# iPlug.net
KiCad netlist of a schematic drawn in EAGLE
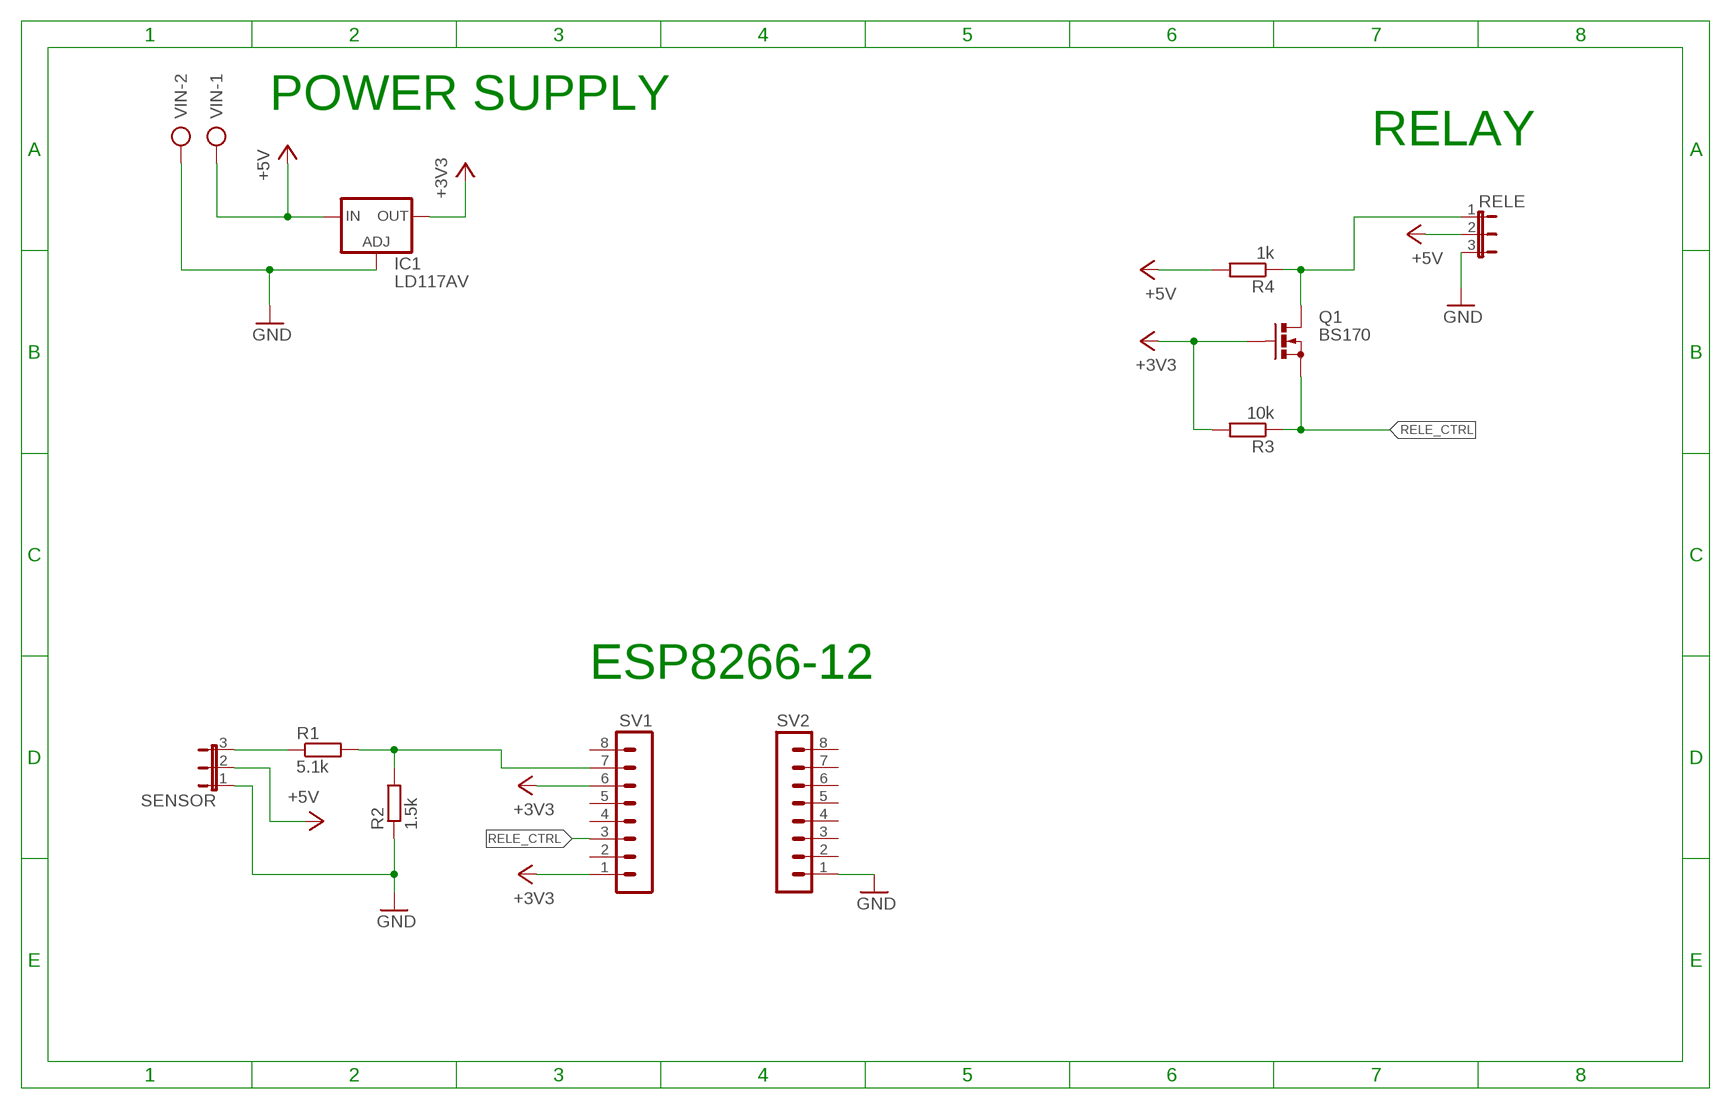
[diagram p0: schematic, sheet 1]

(export (version "E")
  (design (tool "Eeschema 10.0.6"))
  (components
    (comp (ref "IC1")
      (value "LD117AV")
      (footprint "eagle-import:TO220L1")
      (libsource (lib "eagle-import") (part "LD117A?V"))
    )
    (comp (ref "Q1")
      (value "BS170")
      (footprint "eagle-import:SOT54E")
      (libsource (lib "eagle-import") (part "BS170"))
    )
    (comp (ref "R1")
      (value "5.1k")
      (footprint "eagle-import:0207_10")
      (libsource (lib "eagle-import") (part "R-EU_0207/10"))
    )
    (comp (ref "R2")
      (value "1.5k")
      (footprint "eagle-import:0207_10")
      (libsource (lib "eagle-import") (part "R-EU_0207/10"))
    )
    (comp (ref "R3")
      (value "10k")
      (footprint "eagle-import:0207_10")
      (libsource (lib "eagle-import") (part "R-EU_0207/10"))
    )
    (comp (ref "R4")
      (value "1k")
      (footprint "eagle-import:0207_10")
      (libsource (lib "eagle-import") (part "R-EU_0207/10"))
    )
    (comp (ref "RELE")
      (value "JP2E")
      (footprint "eagle-import:JP2")
      (libsource (lib "eagle-import") (part "JP2E"))
    )
    (comp (ref "SENSOR")
      (value "JP2E")
      (footprint "eagle-import:JP2")
      (libsource (lib "eagle-import") (part "JP2E"))
    )
    (comp (ref "SV1")
      (value "MA08-1")
      (footprint "eagle-import:MA08-1")
      (libsource (lib "eagle-import") (part "MA08-1"))
    )
    (comp (ref "SV2")
      (value "MA08-1")
      (footprint "eagle-import:MA08-1")
      (libsource (lib "eagle-import") (part "MA08-1"))
    )
    (comp (ref "VIN")
      (value "AK500/2")
      (footprint "eagle-import:AK500_2")
      (libsource (lib "eagle-import") (part "AK500/2"))
    )
  )
  (nets
    (net (code "1") (name "+3V3") (class "Default")
      (node (ref "IC1") (pin "2") (pinfunction "OUT_2") (pintype "passive"))
      (node (ref "Q1") (pin "G") (pinfunction "G_G") (pintype "passive"))
      (node (ref "R3") (pin "2") (pinfunction "2_2") (pintype "passive"))
      (node (ref "SV1") (pin "1") (pinfunction "1_1") (pintype "passive"))
      (node (ref "SV1") (pin "6") (pinfunction "6_6") (pintype "passive"))
    )
    (net (code "2") (name "+5V") (class "Default")
      (node (ref "IC1") (pin "3") (pinfunction "IN_3") (pintype "input"))
      (node (ref "R4") (pin "2") (pinfunction "2_2") (pintype "passive"))
      (node (ref "RELE") (pin "2") (pinfunction "2_2") (pintype "passive"))
      (node (ref "SENSOR") (pin "2") (pinfunction "2_2") (pintype "passive"))
      (node (ref "VIN") (pin "1") (pinfunction "KL_1") (pintype "passive"))
    )
    (net (code "3") (name "GND") (class "Default")
      (node (ref "IC1") (pin "1") (pinfunction "ADJ_1") (pintype "input"))
      (node (ref "R2") (pin "1") (pinfunction "1_1") (pintype "passive"))
      (node (ref "RELE") (pin "3") (pinfunction "3_3") (pintype "passive"))
      (node (ref "SENSOR") (pin "1") (pinfunction "1_1") (pintype "passive"))
      (node (ref "SV2") (pin "1") (pinfunction "1_1") (pintype "passive"))
      (node (ref "VIN") (pin "2") (pinfunction "KL_2") (pintype "passive"))
    )
    (net (code "4") (name "Net-(Q1-PadD)") (class "Default")
      (node (ref "Q1") (pin "D") (pinfunction "D_D") (pintype "passive"))
      (node (ref "R4") (pin "1") (pinfunction "1_1") (pintype "passive"))
      (node (ref "RELE") (pin "1") (pinfunction "1_1") (pintype "passive"))
    )
    (net (code "5") (name "Net-(R1-Pad1)") (class "Default")
      (node (ref "R1") (pin "1") (pinfunction "1_1") (pintype "passive"))
      (node (ref "SENSOR") (pin "3") (pinfunction "3_3") (pintype "passive"))
    )
    (net (code "6") (name "Net-(R1-Pad2)") (class "Default")
      (node (ref "R1") (pin "2") (pinfunction "2_2") (pintype "passive"))
      (node (ref "R2") (pin "2") (pinfunction "2_2") (pintype "passive"))
      (node (ref "SV1") (pin "7") (pinfunction "7_7") (pintype "passive"))
    )
    (net (code "7") (name "RELE_CTRL") (class "Default")
      (node (ref "Q1") (pin "S") (pinfunction "S_S") (pintype "passive"))
      (node (ref "R3") (pin "1") (pinfunction "1_1") (pintype "passive"))
      (node (ref "SV1") (pin "3") (pinfunction "3_3") (pintype "passive"))
    )
    (net (code "8") (name "unconnected-(SV1-Pad2)") (class "Default")
      (node (ref "SV1") (pin "2") (pinfunction "2_2") (pintype "passive"))
    )
    (net (code "9") (name "unconnected-(SV1-Pad4)") (class "Default")
      (node (ref "SV1") (pin "4") (pinfunction "4_4") (pintype "passive"))
    )
    (net (code "10") (name "unconnected-(SV1-Pad5)") (class "Default")
      (node (ref "SV1") (pin "5") (pinfunction "5_5") (pintype "passive"))
    )
    (net (code "11") (name "unconnected-(SV1-Pad8)") (class "Default")
      (node (ref "SV1") (pin "8") (pinfunction "8_8") (pintype "passive"))
    )
    (net (code "12") (name "unconnected-(SV2-Pad2)") (class "Default")
      (node (ref "SV2") (pin "2") (pinfunction "2_2") (pintype "passive"))
    )
    (net (code "13") (name "unconnected-(SV2-Pad3)") (class "Default")
      (node (ref "SV2") (pin "3") (pinfunction "3_3") (pintype "passive"))
    )
    (net (code "14") (name "unconnected-(SV2-Pad4)") (class "Default")
      (node (ref "SV2") (pin "4") (pinfunction "4_4") (pintype "passive"))
    )
    (net (code "15") (name "unconnected-(SV2-Pad5)") (class "Default")
      (node (ref "SV2") (pin "5") (pinfunction "5_5") (pintype "passive"))
    )
    (net (code "16") (name "unconnected-(SV2-Pad6)") (class "Default")
      (node (ref "SV2") (pin "6") (pinfunction "6_6") (pintype "passive"))
    )
    (net (code "17") (name "unconnected-(SV2-Pad7)") (class "Default")
      (node (ref "SV2") (pin "7") (pinfunction "7_7") (pintype "passive"))
    )
    (net (code "18") (name "unconnected-(SV2-Pad8)") (class "Default")
      (node (ref "SV2") (pin "8") (pinfunction "8_8") (pintype "passive"))
    )
  )
)
